# Sheet2.net
KiCad netlist of a schematic drawn in Altium Designer
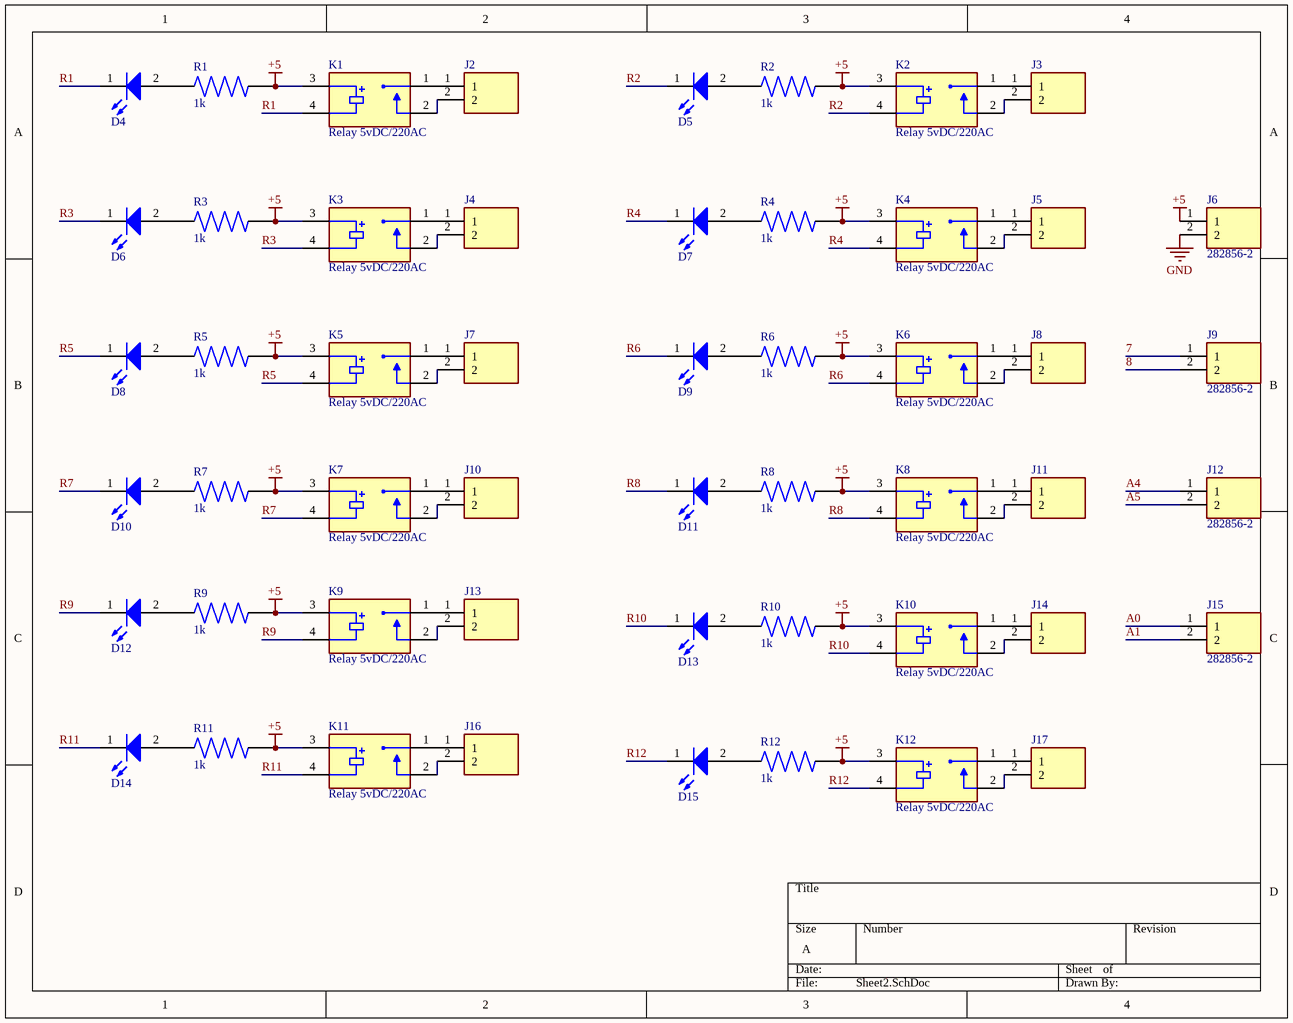
[diagram p0: Sheet2.SchDoc]

(export (version "E")
  (design (tool "Eeschema 10.0.6"))
  (components
    (comp (ref "D4")
      (value "Infrared, 1.4V, 140°")
      (footprint "WL-SICW_0805_L2W1.3H0.8")
      (description "WL-SICW SMT Chip LED Infrared Waterclear, size 1206, Infrared, 1.4V, 140°")
      (fields
        (field (name "MANUFACTURER PART NUMBER") "15412085BA400")
        (field (name "MANUFACTURER") "Wurth Elektronik")
      )
      (libsource (lib "input") (part "15412085BA400"))
    )
    (comp (ref "D5")
      (value "Infrared, 1.4V, 140°")
      (footprint "WL-SICW_0805_L2W1.3H0.8")
      (description "WL-SICW SMT Chip LED Infrared Waterclear, size 1206, Infrared, 1.4V, 140°")
      (fields
        (field (name "MANUFACTURER PART NUMBER") "15412085BA400")
        (field (name "MANUFACTURER") "Wurth Elektronik")
      )
      (libsource (lib "input") (part "15412085BA400"))
    )
    (comp (ref "D6")
      (value "Infrared, 1.4V, 140°")
      (footprint "WL-SICW_0805_L2W1.3H0.8")
      (description "WL-SICW SMT Chip LED Infrared Waterclear, size 1206, Infrared, 1.4V, 140°")
      (fields
        (field (name "MANUFACTURER PART NUMBER") "15412085BA400")
        (field (name "MANUFACTURER") "Wurth Elektronik")
      )
      (libsource (lib "input") (part "15412085BA400"))
    )
    (comp (ref "D7")
      (value "Infrared, 1.4V, 140°")
      (footprint "WL-SICW_0805_L2W1.3H0.8")
      (description "WL-SICW SMT Chip LED Infrared Waterclear, size 1206, Infrared, 1.4V, 140°")
      (fields
        (field (name "MANUFACTURER PART NUMBER") "15412085BA400")
        (field (name "MANUFACTURER") "Wurth Elektronik")
      )
      (libsource (lib "input") (part "15412085BA400"))
    )
    (comp (ref "D8")
      (value "Infrared, 1.4V, 140°")
      (footprint "WL-SICW_0805_L2W1.3H0.8")
      (description "WL-SICW SMT Chip LED Infrared Waterclear, size 1206, Infrared, 1.4V, 140°")
      (fields
        (field (name "MANUFACTURER PART NUMBER") "15412085BA400")
        (field (name "MANUFACTURER") "Wurth Elektronik")
      )
      (libsource (lib "input") (part "15412085BA400"))
    )
    (comp (ref "D9")
      (value "Infrared, 1.4V, 140°")
      (footprint "WL-SICW_0805_L2W1.3H0.8")
      (description "WL-SICW SMT Chip LED Infrared Waterclear, size 1206, Infrared, 1.4V, 140°")
      (fields
        (field (name "MANUFACTURER PART NUMBER") "15412085BA400")
        (field (name "MANUFACTURER") "Wurth Elektronik")
      )
      (libsource (lib "input") (part "15412085BA400"))
    )
    (comp (ref "D10")
      (value "Infrared, 1.4V, 140°")
      (footprint "WL-SICW_0805_L2W1.3H0.8")
      (description "WL-SICW SMT Chip LED Infrared Waterclear, size 1206, Infrared, 1.4V, 140°")
      (fields
        (field (name "MANUFACTURER PART NUMBER") "15412085BA400")
        (field (name "MANUFACTURER") "Wurth Elektronik")
      )
      (libsource (lib "input") (part "15412085BA400"))
    )
    (comp (ref "D11")
      (value "Infrared, 1.4V, 140°")
      (footprint "WL-SICW_0805_L2W1.3H0.8")
      (description "WL-SICW SMT Chip LED Infrared Waterclear, size 1206, Infrared, 1.4V, 140°")
      (fields
        (field (name "MANUFACTURER PART NUMBER") "15412085BA400")
        (field (name "MANUFACTURER") "Wurth Elektronik")
      )
      (libsource (lib "input") (part "15412085BA400"))
    )
    (comp (ref "D12")
      (value "Infrared, 1.4V, 140°")
      (footprint "WL-SICW_0805_L2W1.3H0.8")
      (description "WL-SICW SMT Chip LED Infrared Waterclear, size 1206, Infrared, 1.4V, 140°")
      (fields
        (field (name "MANUFACTURER PART NUMBER") "15412085BA400")
        (field (name "MANUFACTURER") "Wurth Elektronik")
      )
      (libsource (lib "input") (part "15412085BA400"))
    )
    (comp (ref "D13")
      (value "Infrared, 1.4V, 140°")
      (footprint "WL-SICW_0805_L2W1.3H0.8")
      (description "WL-SICW SMT Chip LED Infrared Waterclear, size 1206, Infrared, 1.4V, 140°")
      (fields
        (field (name "MANUFACTURER PART NUMBER") "15412085BA400")
        (field (name "MANUFACTURER") "Wurth Elektronik")
      )
      (libsource (lib "input") (part "15412085BA400"))
    )
    (comp (ref "D14")
      (value "Infrared, 1.4V, 140°")
      (footprint "WL-SICW_0805_L2W1.3H0.8")
      (description "WL-SICW SMT Chip LED Infrared Waterclear, size 1206, Infrared, 1.4V, 140°")
      (fields
        (field (name "MANUFACTURER PART NUMBER") "15412085BA400")
        (field (name "MANUFACTURER") "Wurth Elektronik")
      )
      (libsource (lib "input") (part "15412085BA400"))
    )
    (comp (ref "D15")
      (value "Infrared, 1.4V, 140°")
      (footprint "WL-SICW_0805_L2W1.3H0.8")
      (description "WL-SICW SMT Chip LED Infrared Waterclear, size 1206, Infrared, 1.4V, 140°")
      (fields
        (field (name "MANUFACTURER PART NUMBER") "15412085BA400")
        (field (name "MANUFACTURER") "Wurth Elektronik")
      )
      (libsource (lib "input") (part "15412085BA400"))
    )
    (comp (ref "J2")
      (value "282856-2")
      (footprint "TE_282856-2")
      (description "TERMI-BLOK PCB MOUNT 2P")
      (fields (field (name "MF") "TE Connectivity"))
      (libsource (lib "input") (part "282856-2"))
    )
    (comp (ref "J3")
      (value "282856-2")
      (footprint "TE_282856-2")
      (description "TERMI-BLOK PCB MOUNT 2P")
      (fields (field (name "MF") "TE Connectivity"))
      (libsource (lib "input") (part "282856-2"))
    )
    (comp (ref "J4")
      (value "282856-2")
      (footprint "TE_282856-2")
      (description "TERMI-BLOK PCB MOUNT 2P")
      (fields (field (name "MF") "TE Connectivity"))
      (libsource (lib "input") (part "282856-2"))
    )
    (comp (ref "J5")
      (value "282856-2")
      (footprint "TE_282856-2")
      (description "TERMI-BLOK PCB MOUNT 2P")
      (fields (field (name "MF") "TE Connectivity"))
      (libsource (lib "input") (part "282856-2"))
    )
    (comp (ref "J6")
      (value "282856-2")
      (footprint "TE_282856-2")
      (description "TERMI-BLOK PCB MOUNT 2P")
      (fields (field (name "MF") "TE Connectivity"))
      (libsource (lib "input") (part "282856-2"))
    )
    (comp (ref "J7")
      (value "282856-2")
      (footprint "TE_282856-2")
      (description "TERMI-BLOK PCB MOUNT 2P")
      (fields (field (name "MF") "TE Connectivity"))
      (libsource (lib "input") (part "282856-2"))
    )
    (comp (ref "J8")
      (value "282856-2")
      (footprint "TE_282856-2")
      (description "TERMI-BLOK PCB MOUNT 2P")
      (fields (field (name "MF") "TE Connectivity"))
      (libsource (lib "input") (part "282856-2"))
    )
    (comp (ref "J9")
      (value "282856-2")
      (footprint "TE_282856-2")
      (description "TERMI-BLOK PCB MOUNT 2P")
      (fields (field (name "MF") "TE Connectivity"))
      (libsource (lib "input") (part "282856-2"))
    )
    (comp (ref "J10")
      (value "282856-2")
      (footprint "TE_282856-2")
      (description "TERMI-BLOK PCB MOUNT 2P")
      (fields (field (name "MF") "TE Connectivity"))
      (libsource (lib "input") (part "282856-2"))
    )
    (comp (ref "J11")
      (value "282856-2")
      (footprint "TE_282856-2")
      (description "TERMI-BLOK PCB MOUNT 2P")
      (fields (field (name "MF") "TE Connectivity"))
      (libsource (lib "input") (part "282856-2"))
    )
    (comp (ref "J12")
      (value "282856-2")
      (footprint "TE_282856-2")
      (description "TERMI-BLOK PCB MOUNT 2P")
      (fields (field (name "MF") "TE Connectivity"))
      (libsource (lib "input") (part "282856-2"))
    )
    (comp (ref "J13")
      (value "282856-2")
      (footprint "TE_282856-2")
      (description "TERMI-BLOK PCB MOUNT 2P")
      (fields (field (name "MF") "TE Connectivity"))
      (libsource (lib "input") (part "282856-2"))
    )
    (comp (ref "J14")
      (value "282856-2")
      (footprint "TE_282856-2")
      (description "TERMI-BLOK PCB MOUNT 2P")
      (fields (field (name "MF") "TE Connectivity"))
      (libsource (lib "input") (part "282856-2"))
    )
    (comp (ref "J15")
      (value "282856-2")
      (footprint "TE_282856-2")
      (description "TERMI-BLOK PCB MOUNT 2P")
      (fields (field (name "MF") "TE Connectivity"))
      (libsource (lib "input") (part "282856-2"))
    )
    (comp (ref "J16")
      (value "282856-2")
      (footprint "TE_282856-2")
      (description "TERMI-BLOK PCB MOUNT 2P")
      (fields (field (name "MF") "TE Connectivity"))
      (libsource (lib "input") (part "282856-2"))
    )
    (comp (ref "J17")
      (value "282856-2")
      (footprint "TE_282856-2")
      (description "TERMI-BLOK PCB MOUNT 2P")
      (fields (field (name "MF") "TE Connectivity"))
      (libsource (lib "input") (part "282856-2"))
    )
    (comp (ref "K1")
      (value "Relay 5vDC/220AC")
      (footprint "control:RELAY_G3MB-202PDC5")
      (description "Solid State SPST-NO (1 Form A) 4-SIP")
      (fields (field (name "MP") "G3MB-202P DC5") (field (name "MF") "Omron Automation"))
      (libsource (lib "control") (part "G3MB-202PDC5"))
    )
    (comp (ref "K2")
      (value "Relay 5vDC/220AC")
      (footprint "control:RELAY_G3MB-202PDC5")
      (description "Solid State SPST-NO (1 Form A) 4-SIP")
      (fields (field (name "MP") "G3MB-202P DC5") (field (name "MF") "Omron Automation"))
      (libsource (lib "control") (part "G3MB-202PDC5"))
    )
    (comp (ref "K3")
      (value "Relay 5vDC/220AC")
      (footprint "control:RELAY_G3MB-202PDC5")
      (description "Solid State SPST-NO (1 Form A) 4-SIP")
      (fields (field (name "MP") "G3MB-202P DC5") (field (name "MF") "Omron Automation"))
      (libsource (lib "control") (part "G3MB-202PDC5"))
    )
    (comp (ref "K4")
      (value "Relay 5vDC/220AC")
      (footprint "control:RELAY_G3MB-202PDC5")
      (description "Solid State SPST-NO (1 Form A) 4-SIP")
      (fields (field (name "MP") "G3MB-202P DC5") (field (name "MF") "Omron Automation"))
      (libsource (lib "control") (part "G3MB-202PDC5"))
    )
    (comp (ref "K5")
      (value "Relay 5vDC/220AC")
      (footprint "control:RELAY_G3MB-202PDC5")
      (description "Solid State SPST-NO (1 Form A) 4-SIP")
      (fields (field (name "MP") "G3MB-202P DC5") (field (name "MF") "Omron Automation"))
      (libsource (lib "control") (part "G3MB-202PDC5"))
    )
    (comp (ref "K6")
      (value "Relay 5vDC/220AC")
      (footprint "control:RELAY_G3MB-202PDC5")
      (description "Solid State SPST-NO (1 Form A) 4-SIP")
      (fields (field (name "MP") "G3MB-202P DC5") (field (name "MF") "Omron Automation"))
      (libsource (lib "control") (part "G3MB-202PDC5"))
    )
    (comp (ref "K7")
      (value "Relay 5vDC/220AC")
      (footprint "control:RELAY_G3MB-202PDC5")
      (description "Solid State SPST-NO (1 Form A) 4-SIP")
      (fields (field (name "MP") "G3MB-202P DC5") (field (name "MF") "Omron Automation"))
      (libsource (lib "control") (part "G3MB-202PDC5"))
    )
    (comp (ref "K8")
      (value "Relay 5vDC/220AC")
      (footprint "control:RELAY_G3MB-202PDC5")
      (description "Solid State SPST-NO (1 Form A) 4-SIP")
      (fields (field (name "MP") "G3MB-202P DC5") (field (name "MF") "Omron Automation"))
      (libsource (lib "control") (part "G3MB-202PDC5"))
    )
    (comp (ref "K9")
      (value "Relay 5vDC/220AC")
      (footprint "control:RELAY_G3MB-202PDC5")
      (description "Solid State SPST-NO (1 Form A) 4-SIP")
      (fields (field (name "MP") "G3MB-202P DC5") (field (name "MF") "Omron Automation"))
      (libsource (lib "control") (part "G3MB-202PDC5"))
    )
    (comp (ref "K10")
      (value "Relay 5vDC/220AC")
      (footprint "control:RELAY_G3MB-202PDC5")
      (description "Solid State SPST-NO (1 Form A) 4-SIP")
      (fields (field (name "MP") "G3MB-202P DC5") (field (name "MF") "Omron Automation"))
      (libsource (lib "control") (part "G3MB-202PDC5"))
    )
    (comp (ref "K11")
      (value "Relay 5vDC/220AC")
      (footprint "control:RELAY_G3MB-202PDC5")
      (description "Solid State SPST-NO (1 Form A) 4-SIP")
      (fields (field (name "MP") "G3MB-202P DC5") (field (name "MF") "Omron Automation"))
      (libsource (lib "control") (part "G3MB-202PDC5"))
    )
    (comp (ref "K12")
      (value "Relay 5vDC/220AC")
      (footprint "control:RELAY_G3MB-202PDC5")
      (description "Solid State SPST-NO (1 Form A) 4-SIP")
      (fields (field (name "MP") "G3MB-202P DC5") (field (name "MF") "Omron Automation"))
      (libsource (lib "control") (part "G3MB-202PDC5"))
    )
    (comp (ref "R1")
      (value "1k")
      (footprint "RESC3216X70N")
      (description "Res 1206 10 Ohm 5% 1/8W Â±500ppm/Â°C Molded SMD SMD T/R")
      (fields (field (name "TOLERANCE") "5%") (field (name "MP") "FCR1206J10R"))
      (libsource (lib "input") (part "FCR1206J10R"))
    )
    (comp (ref "R2")
      (value "1k")
      (footprint "RESC3216X70N")
      (description "Res 1206 10 Ohm 5% 1/8W Â±500ppm/Â°C Molded SMD SMD T/R")
      (fields (field (name "TOLERANCE") "5%") (field (name "MP") "FCR1206J10R"))
      (libsource (lib "input") (part "FCR1206J10R"))
    )
    (comp (ref "R3")
      (value "1k")
      (footprint "RESC3216X70N")
      (description "Res 1206 10 Ohm 5% 1/8W Â±500ppm/Â°C Molded SMD SMD T/R")
      (fields (field (name "TOLERANCE") "5%") (field (name "MP") "FCR1206J10R"))
      (libsource (lib "input") (part "FCR1206J10R"))
    )
    (comp (ref "R4")
      (value "1k")
      (footprint "RESC3216X70N")
      (description "Res 1206 10 Ohm 5% 1/8W Â±500ppm/Â°C Molded SMD SMD T/R")
      (fields (field (name "TOLERANCE") "5%") (field (name "MP") "FCR1206J10R"))
      (libsource (lib "input") (part "FCR1206J10R"))
    )
    (comp (ref "R5")
      (value "1k")
      (footprint "RESC3216X70N")
      (description "Res 1206 10 Ohm 5% 1/8W Â±500ppm/Â°C Molded SMD SMD T/R")
      (fields (field (name "TOLERANCE") "5%") (field (name "MP") "FCR1206J10R"))
      (libsource (lib "input") (part "FCR1206J10R"))
    )
    (comp (ref "R6")
      (value "1k")
      (footprint "RESC3216X70N")
      (description "Res 1206 10 Ohm 5% 1/8W Â±500ppm/Â°C Molded SMD SMD T/R")
      (fields (field (name "TOLERANCE") "5%") (field (name "MP") "FCR1206J10R"))
      (libsource (lib "input") (part "FCR1206J10R"))
    )
    (comp (ref "R7")
      (value "1k")
      (footprint "RESC3216X70N")
      (description "Res 1206 10 Ohm 5% 1/8W Â±500ppm/Â°C Molded SMD SMD T/R")
      (fields (field (name "TOLERANCE") "5%") (field (name "MP") "FCR1206J10R"))
      (libsource (lib "input") (part "FCR1206J10R"))
    )
    (comp (ref "R8")
      (value "1k")
      (footprint "RESC3216X70N")
      (description "Res 1206 10 Ohm 5% 1/8W Â±500ppm/Â°C Molded SMD SMD T/R")
      (fields (field (name "TOLERANCE") "5%") (field (name "MP") "FCR1206J10R"))
      (libsource (lib "input") (part "FCR1206J10R"))
    )
    (comp (ref "R9")
      (value "1k")
      (footprint "RESC3216X70N")
      (description "Res 1206 10 Ohm 5% 1/8W Â±500ppm/Â°C Molded SMD SMD T/R")
      (fields (field (name "TOLERANCE") "5%") (field (name "MP") "FCR1206J10R"))
      (libsource (lib "input") (part "FCR1206J10R"))
    )
    (comp (ref "R10")
      (value "1k")
      (footprint "RESC3216X70N")
      (description "Res 1206 10 Ohm 5% 1/8W Â±500ppm/Â°C Molded SMD SMD T/R")
      (fields (field (name "TOLERANCE") "5%") (field (name "MP") "FCR1206J10R"))
      (libsource (lib "input") (part "FCR1206J10R"))
    )
    (comp (ref "R11")
      (value "1k")
      (footprint "RESC3216X70N")
      (description "Res 1206 10 Ohm 5% 1/8W Â±500ppm/Â°C Molded SMD SMD T/R")
      (fields (field (name "TOLERANCE") "5%") (field (name "MP") "FCR1206J10R"))
      (libsource (lib "input") (part "FCR1206J10R"))
    )
    (comp (ref "R12")
      (value "1k")
      (footprint "RESC3216X70N")
      (description "Res 1206 10 Ohm 5% 1/8W Â±500ppm/Â°C Molded SMD SMD T/R")
      (fields (field (name "TOLERANCE") "5%") (field (name "MP") "FCR1206J10R"))
      (libsource (lib "input") (part "FCR1206J10R"))
    )
  )
  (nets
    (net (code "1") (name "+5") (class "Default")
      (node (ref "J6") (pin "1") (pinfunction "1_1") (pintype "passive"))
      (node (ref "K1") (pin "3") (pinfunction "3_3") (pintype "passive"))
      (node (ref "K10") (pin "3") (pinfunction "3_3") (pintype "passive"))
      (node (ref "K11") (pin "3") (pinfunction "3_3") (pintype "passive"))
      (node (ref "K12") (pin "3") (pinfunction "3_3") (pintype "passive"))
      (node (ref "K2") (pin "3") (pinfunction "3_3") (pintype "passive"))
      (node (ref "K3") (pin "3") (pinfunction "3_3") (pintype "passive"))
      (node (ref "K4") (pin "3") (pinfunction "3_3") (pintype "passive"))
      (node (ref "K5") (pin "3") (pinfunction "3_3") (pintype "passive"))
      (node (ref "K6") (pin "3") (pinfunction "3_3") (pintype "passive"))
      (node (ref "K7") (pin "3") (pinfunction "3_3") (pintype "passive"))
      (node (ref "K8") (pin "3") (pinfunction "3_3") (pintype "passive"))
      (node (ref "K9") (pin "3") (pinfunction "3_3") (pintype "passive"))
      (node (ref "R1") (pin "2") (pinfunction "2_2") (pintype "passive"))
      (node (ref "R10") (pin "2") (pinfunction "2_2") (pintype "passive"))
      (node (ref "R11") (pin "2") (pinfunction "2_2") (pintype "passive"))
      (node (ref "R12") (pin "2") (pinfunction "2_2") (pintype "passive"))
      (node (ref "R2") (pin "2") (pinfunction "2_2") (pintype "passive"))
      (node (ref "R3") (pin "2") (pinfunction "2_2") (pintype "passive"))
      (node (ref "R4") (pin "2") (pinfunction "2_2") (pintype "passive"))
      (node (ref "R5") (pin "2") (pinfunction "2_2") (pintype "passive"))
      (node (ref "R6") (pin "2") (pinfunction "2_2") (pintype "passive"))
      (node (ref "R7") (pin "2") (pinfunction "2_2") (pintype "passive"))
      (node (ref "R8") (pin "2") (pinfunction "2_2") (pintype "passive"))
      (node (ref "R9") (pin "2") (pinfunction "2_2") (pintype "passive"))
    )
    (net (code "2") (name "/7") (class "Default")
      (node (ref "J9") (pin "1") (pinfunction "1_1") (pintype "passive"))
    )
    (net (code "3") (name "/8") (class "Default")
      (node (ref "J9") (pin "2") (pinfunction "2_2") (pintype "passive"))
    )
    (net (code "5") (name "/A0") (class "Default")
      (node (ref "J15") (pin "1") (pinfunction "1_1") (pintype "passive"))
    )
    (net (code "6") (name "/A1") (class "Default")
      (node (ref "J15") (pin "2") (pinfunction "2_2") (pintype "passive"))
    )
    (net (code "7") (name "/A4") (class "Default")
      (node (ref "J12") (pin "1") (pinfunction "1_1") (pintype "passive"))
    )
    (net (code "8") (name "/A5") (class "Default")
      (node (ref "J12") (pin "2") (pinfunction "2_2") (pintype "passive"))
    )
    (net (code "9") (name "/R1") (class "Default")
      (node (ref "D4") (pin "1") (pinfunction "K_1") (pintype "passive"))
      (node (ref "K1") (pin "4") (pinfunction "4_4") (pintype "passive"))
    )
    (net (code "10") (name "/R2") (class "Default")
      (node (ref "D5") (pin "1") (pinfunction "K_1") (pintype "passive"))
      (node (ref "K2") (pin "4") (pinfunction "4_4") (pintype "passive"))
    )
    (net (code "11") (name "/R3") (class "Default")
      (node (ref "D6") (pin "1") (pinfunction "K_1") (pintype "passive"))
      (node (ref "K3") (pin "4") (pinfunction "4_4") (pintype "passive"))
    )
    (net (code "12") (name "/R4") (class "Default")
      (node (ref "D7") (pin "1") (pinfunction "K_1") (pintype "passive"))
      (node (ref "K4") (pin "4") (pinfunction "4_4") (pintype "passive"))
    )
    (net (code "13") (name "/R5") (class "Default")
      (node (ref "D8") (pin "1") (pinfunction "K_1") (pintype "passive"))
      (node (ref "K5") (pin "4") (pinfunction "4_4") (pintype "passive"))
    )
    (net (code "14") (name "/R6") (class "Default")
      (node (ref "D9") (pin "1") (pinfunction "K_1") (pintype "passive"))
      (node (ref "K6") (pin "4") (pinfunction "4_4") (pintype "passive"))
    )
    (net (code "15") (name "/R7") (class "Default")
      (node (ref "D10") (pin "1") (pinfunction "K_1") (pintype "passive"))
      (node (ref "K7") (pin "4") (pinfunction "4_4") (pintype "passive"))
    )
    (net (code "16") (name "/R8") (class "Default")
      (node (ref "D11") (pin "1") (pinfunction "K_1") (pintype "passive"))
      (node (ref "K8") (pin "4") (pinfunction "4_4") (pintype "passive"))
    )
    (net (code "17") (name "/R9") (class "Default")
      (node (ref "D12") (pin "1") (pinfunction "K_1") (pintype "passive"))
      (node (ref "K9") (pin "4") (pinfunction "4_4") (pintype "passive"))
    )
    (net (code "18") (name "/R10") (class "Default")
      (node (ref "D13") (pin "1") (pinfunction "K_1") (pintype "passive"))
      (node (ref "K10") (pin "4") (pinfunction "4_4") (pintype "passive"))
    )
    (net (code "19") (name "/R11") (class "Default")
      (node (ref "D14") (pin "1") (pinfunction "K_1") (pintype "passive"))
      (node (ref "K11") (pin "4") (pinfunction "4_4") (pintype "passive"))
    )
    (net (code "20") (name "/R12") (class "Default")
      (node (ref "D15") (pin "1") (pinfunction "K_1") (pintype "passive"))
      (node (ref "K12") (pin "4") (pinfunction "4_4") (pintype "passive"))
    )
    (net (code "21") (name "GND") (class "Default")
      (node (ref "J6") (pin "2") (pinfunction "2_2") (pintype "passive"))
    )
    (net (code "22") (name "Net-(D4-A)") (class "Default")
      (node (ref "D4") (pin "2") (pinfunction "A_2") (pintype "passive"))
      (node (ref "R1") (pin "1") (pinfunction "1_1") (pintype "passive"))
    )
    (net (code "23") (name "Net-(D5-A)") (class "Default")
      (node (ref "D5") (pin "2") (pinfunction "A_2") (pintype "passive"))
      (node (ref "R2") (pin "1") (pinfunction "1_1") (pintype "passive"))
    )
    (net (code "24") (name "Net-(D6-A)") (class "Default")
      (node (ref "D6") (pin "2") (pinfunction "A_2") (pintype "passive"))
      (node (ref "R3") (pin "1") (pinfunction "1_1") (pintype "passive"))
    )
    (net (code "25") (name "Net-(D7-A)") (class "Default")
      (node (ref "D7") (pin "2") (pinfunction "A_2") (pintype "passive"))
      (node (ref "R4") (pin "1") (pinfunction "1_1") (pintype "passive"))
    )
    (net (code "26") (name "Net-(D8-A)") (class "Default")
      (node (ref "D8") (pin "2") (pinfunction "A_2") (pintype "passive"))
      (node (ref "R5") (pin "1") (pinfunction "1_1") (pintype "passive"))
    )
    (net (code "27") (name "Net-(D9-A)") (class "Default")
      (node (ref "D9") (pin "2") (pinfunction "A_2") (pintype "passive"))
      (node (ref "R6") (pin "1") (pinfunction "1_1") (pintype "passive"))
    )
    (net (code "28") (name "Net-(D10-A)") (class "Default")
      (node (ref "D10") (pin "2") (pinfunction "A_2") (pintype "passive"))
      (node (ref "R7") (pin "1") (pinfunction "1_1") (pintype "passive"))
    )
    (net (code "29") (name "Net-(D11-A)") (class "Default")
      (node (ref "D11") (pin "2") (pinfunction "A_2") (pintype "passive"))
      (node (ref "R8") (pin "1") (pinfunction "1_1") (pintype "passive"))
    )
    (net (code "30") (name "Net-(D12-A)") (class "Default")
      (node (ref "D12") (pin "2") (pinfunction "A_2") (pintype "passive"))
      (node (ref "R9") (pin "1") (pinfunction "1_1") (pintype "passive"))
    )
    (net (code "31") (name "Net-(D13-A)") (class "Default")
      (node (ref "D13") (pin "2") (pinfunction "A_2") (pintype "passive"))
      (node (ref "R10") (pin "1") (pinfunction "1_1") (pintype "passive"))
    )
    (net (code "32") (name "Net-(D14-A)") (class "Default")
      (node (ref "D14") (pin "2") (pinfunction "A_2") (pintype "passive"))
      (node (ref "R11") (pin "1") (pinfunction "1_1") (pintype "passive"))
    )
    (net (code "33") (name "Net-(D15-A)") (class "Default")
      (node (ref "D15") (pin "2") (pinfunction "A_2") (pintype "passive"))
      (node (ref "R12") (pin "1") (pinfunction "1_1") (pintype "passive"))
    )
    (net (code "34") (name "Net-(J2-Pad1)") (class "Default")
      (node (ref "J2") (pin "1") (pinfunction "1_1") (pintype "passive"))
      (node (ref "K1") (pin "1") (pinfunction "1_1") (pintype "passive"))
    )
    (net (code "35") (name "Net-(J2-Pad2)") (class "Default")
      (node (ref "J2") (pin "2") (pinfunction "2_2") (pintype "passive"))
      (node (ref "K1") (pin "2") (pinfunction "2_2") (pintype "passive"))
    )
    (net (code "36") (name "Net-(J3-Pad1)") (class "Default")
      (node (ref "J3") (pin "1") (pinfunction "1_1") (pintype "passive"))
      (node (ref "K2") (pin "1") (pinfunction "1_1") (pintype "passive"))
    )
    (net (code "37") (name "Net-(J3-Pad2)") (class "Default")
      (node (ref "J3") (pin "2") (pinfunction "2_2") (pintype "passive"))
      (node (ref "K2") (pin "2") (pinfunction "2_2") (pintype "passive"))
    )
    (net (code "38") (name "Net-(J4-Pad1)") (class "Default")
      (node (ref "J4") (pin "1") (pinfunction "1_1") (pintype "passive"))
      (node (ref "K3") (pin "1") (pinfunction "1_1") (pintype "passive"))
    )
    (net (code "39") (name "Net-(J4-Pad2)") (class "Default")
      (node (ref "J4") (pin "2") (pinfunction "2_2") (pintype "passive"))
      (node (ref "K3") (pin "2") (pinfunction "2_2") (pintype "passive"))
    )
    (net (code "40") (name "Net-(J5-Pad1)") (class "Default")
      (node (ref "J5") (pin "1") (pinfunction "1_1") (pintype "passive"))
      (node (ref "K4") (pin "1") (pinfunction "1_1") (pintype "passive"))
    )
    (net (code "41") (name "Net-(J5-Pad2)") (class "Default")
      (node (ref "J5") (pin "2") (pinfunction "2_2") (pintype "passive"))
      (node (ref "K4") (pin "2") (pinfunction "2_2") (pintype "passive"))
    )
    (net (code "42") (name "Net-(J7-Pad1)") (class "Default")
      (node (ref "J7") (pin "1") (pinfunction "1_1") (pintype "passive"))
      (node (ref "K5") (pin "1") (pinfunction "1_1") (pintype "passive"))
    )
    (net (code "43") (name "Net-(J7-Pad2)") (class "Default")
      (node (ref "J7") (pin "2") (pinfunction "2_2") (pintype "passive"))
      (node (ref "K5") (pin "2") (pinfunction "2_2") (pintype "passive"))
    )
    (net (code "44") (name "Net-(J8-Pad1)") (class "Default")
      (node (ref "J8") (pin "1") (pinfunction "1_1") (pintype "passive"))
      (node (ref "K6") (pin "1") (pinfunction "1_1") (pintype "passive"))
    )
    (net (code "45") (name "Net-(J8-Pad2)") (class "Default")
      (node (ref "J8") (pin "2") (pinfunction "2_2") (pintype "passive"))
      (node (ref "K6") (pin "2") (pinfunction "2_2") (pintype "passive"))
    )
    (net (code "46") (name "Net-(J10-Pad1)") (class "Default")
      (node (ref "J10") (pin "1") (pinfunction "1_1") (pintype "passive"))
      (node (ref "K7") (pin "1") (pinfunction "1_1") (pintype "passive"))
    )
    (net (code "47") (name "Net-(J10-Pad2)") (class "Default")
      (node (ref "J10") (pin "2") (pinfunction "2_2") (pintype "passive"))
      (node (ref "K7") (pin "2") (pinfunction "2_2") (pintype "passive"))
    )
    (net (code "48") (name "Net-(J11-Pad1)") (class "Default")
      (node (ref "J11") (pin "1") (pinfunction "1_1") (pintype "passive"))
      (node (ref "K8") (pin "1") (pinfunction "1_1") (pintype "passive"))
    )
    (net (code "49") (name "Net-(J11-Pad2)") (class "Default")
      (node (ref "J11") (pin "2") (pinfunction "2_2") (pintype "passive"))
      (node (ref "K8") (pin "2") (pinfunction "2_2") (pintype "passive"))
    )
    (net (code "50") (name "Net-(J13-Pad1)") (class "Default")
      (node (ref "J13") (pin "1") (pinfunction "1_1") (pintype "passive"))
      (node (ref "K9") (pin "1") (pinfunction "1_1") (pintype "passive"))
    )
    (net (code "51") (name "Net-(J13-Pad2)") (class "Default")
      (node (ref "J13") (pin "2") (pinfunction "2_2") (pintype "passive"))
      (node (ref "K9") (pin "2") (pinfunction "2_2") (pintype "passive"))
    )
    (net (code "52") (name "Net-(J14-Pad1)") (class "Default")
      (node (ref "J14") (pin "1") (pinfunction "1_1") (pintype "passive"))
      (node (ref "K10") (pin "1") (pinfunction "1_1") (pintype "passive"))
    )
    (net (code "53") (name "Net-(J14-Pad2)") (class "Default")
      (node (ref "J14") (pin "2") (pinfunction "2_2") (pintype "passive"))
      (node (ref "K10") (pin "2") (pinfunction "2_2") (pintype "passive"))
    )
    (net (code "54") (name "Net-(J16-Pad1)") (class "Default")
      (node (ref "J16") (pin "1") (pinfunction "1_1") (pintype "passive"))
      (node (ref "K11") (pin "1") (pinfunction "1_1") (pintype "passive"))
    )
    (net (code "55") (name "Net-(J16-Pad2)") (class "Default")
      (node (ref "J16") (pin "2") (pinfunction "2_2") (pintype "passive"))
      (node (ref "K11") (pin "2") (pinfunction "2_2") (pintype "passive"))
    )
    (net (code "56") (name "Net-(J17-Pad1)") (class "Default")
      (node (ref "J17") (pin "1") (pinfunction "1_1") (pintype "passive"))
      (node (ref "K12") (pin "1") (pinfunction "1_1") (pintype "passive"))
    )
    (net (code "57") (name "Net-(J17-Pad2)") (class "Default")
      (node (ref "J17") (pin "2") (pinfunction "2_2") (pintype "passive"))
      (node (ref "K12") (pin "2") (pinfunction "2_2") (pintype "passive"))
    )
  )
)
